# USB.net
KiCad netlist of a schematic drawn in Altium Designer
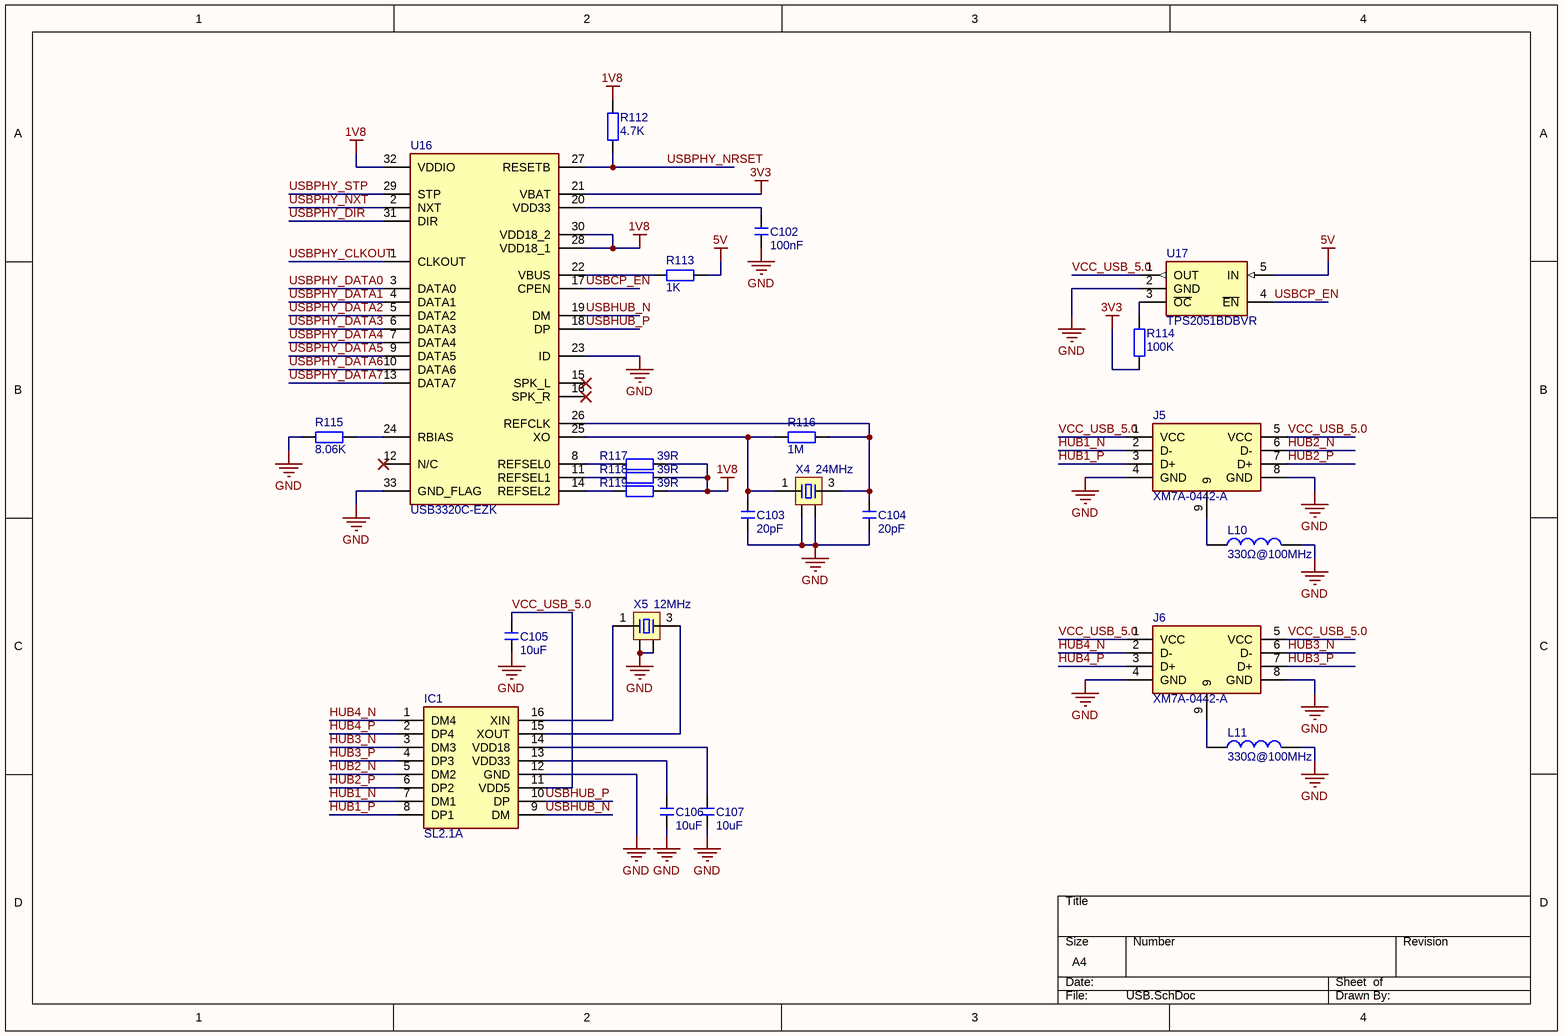
[diagram p0: USB.SchDoc]

(export (version "E")
  (design (tool "Eeschema 10.0.6"))
  (components
    (comp (ref "C102")
      (value "100nF")
      (footprint "C 0402_L")
      (description "无极性贴片电容")
      (fields (field (name "版权归属") "源创客"))
      (libsource (lib "3.1   - 电阻-电容-电感") (part "C"))
    )
    (comp (ref "C103")
      (value "20pF")
      (footprint "C 0805_L")
      (description "无极性贴片电容")
      (fields (field (name "版权归属") "源创客"))
      (libsource (lib "3.1   - 电阻-电容-电感") (part "C"))
    )
    (comp (ref "C104")
      (value "20pF")
      (footprint "C 0805_L")
      (description "无极性贴片电容")
      (fields (field (name "版权归属") "源创客"))
      (libsource (lib "3.1   - 电阻-电容-电感") (part "C"))
    )
    (comp (ref "C105")
      (value "10uF")
      (footprint "C 0603_L")
      (description "无极性贴片电容")
      (fields (field (name "版权归属") "源创客"))
      (libsource (lib "3.1   - 电阻-电容-电感") (part "C"))
    )
    (comp (ref "C106")
      (value "10uF")
      (footprint "C 0603_L")
      (description "无极性贴片电容")
      (fields (field (name "版权归属") "源创客"))
      (libsource (lib "3.1   - 电阻-电容-电感") (part "C"))
    )
    (comp (ref "C107")
      (value "10uF")
      (footprint "C 0603_L")
      (description "无极性贴片电容")
      (fields (field (name "版权归属") "源创客"))
      (libsource (lib "3.1   - 电阻-电容-电感") (part "C"))
    )
    (comp (ref "IC1")
      (value "SL2.1A")
      (footprint "SOP16N_L")
      (description "Integrated Circuit")
      (libsource (lib "1.1   - IC芯片") (part "SL2.1A"))
    )
    (comp (ref "J5")
      (value "XM7A-0442-A")
      (footprint "XM7A0442A")
      (description "USB2.0-A双层")
      (fields (field (name "MOUSER PART NUMBER") "653-XM7A-0442A"))
      (libsource (lib "4.1   - 接口类") (part "XM7A-0442-A"))
    )
    (comp (ref "J6")
      (value "XM7A-0442-A")
      (footprint "XM7A0442A")
      (description "USB2.0-A双层")
      (fields (field (name "MOUSER PART NUMBER") "653-XM7A-0442A"))
      (libsource (lib "4.1   - 接口类") (part "XM7A-0442-A"))
    )
    (comp (ref "L10")
      (value "330Ω@100MHz")
      (footprint "L 0805")
      (description "小功率贴片电感")
      (fields (field (name "版权归属") "源创客"))
      (libsource (lib "3.1   - 电阻-电容-电感") (part "L"))
    )
    (comp (ref "L11")
      (value "330Ω@100MHz")
      (footprint "L 0805")
      (description "小功率贴片电感")
      (fields (field (name "版权归属") "源创客"))
      (libsource (lib "3.1   - 电阻-电容-电感") (part "L"))
    )
    (comp (ref "R112")
      (value "4.7K")
      (footprint "R 0402_L")
      (description "贴片电阻")
      (fields (field (name "版权归属") "源创客"))
      (libsource (lib "3.1   - 电阻-电容-电感") (part "R"))
    )
    (comp (ref "R113")
      (value "1K")
      (footprint "R 0402_L")
      (description "贴片电阻")
      (fields (field (name "版权归属") "源创客"))
      (libsource (lib "3.1   - 电阻-电容-电感") (part "R"))
    )
    (comp (ref "R114")
      (value "100K")
      (footprint "R 0805_L")
      (description "贴片电阻")
      (fields (field (name "版权归属") "源创客"))
      (libsource (lib "3.1   - 电阻-电容-电感") (part "R"))
    )
    (comp (ref "R115")
      (value "8.06K")
      (footprint "R 0402_L")
      (description "贴片电阻")
      (fields (field (name "版权归属") "源创客"))
      (libsource (lib "3.1   - 电阻-电容-电感") (part "R"))
    )
    (comp (ref "R116")
      (value "1M")
      (footprint "R 0402_L")
      (description "贴片电阻")
      (fields (field (name "版权归属") "源创客"))
      (libsource (lib "3.1   - 电阻-电容-电感") (part "R"))
    )
    (comp (ref "R117")
      (value "39R")
      (footprint "R 0805_L")
      (description "贴片电阻")
      (fields (field (name "版权归属") "源创客"))
      (libsource (lib "3.1   - 电阻-电容-电感") (part "R"))
    )
    (comp (ref "R118")
      (value "39R")
      (footprint "R 0805_L")
      (description "贴片电阻")
      (fields (field (name "版权归属") "源创客"))
      (libsource (lib "3.1   - 电阻-电容-电感") (part "R"))
    )
    (comp (ref "R119")
      (value "39R")
      (footprint "R 0805_L")
      (description "贴片电阻")
      (fields (field (name "版权归属") "源创客"))
      (libsource (lib "3.1   - 电阻-电容-电感") (part "R"))
    )
    (comp (ref "U16")
      (value "USB3320C-EZK")
      (footprint "QFN32 5x5_M")
      (description "USB集线芯片")
      (fields (field (name "MOUSER PART NUMBER") "886-USB3320C-EZK"))
      (libsource (lib "1.1   - IC芯片") (part "USB3320C-EZK"))
    )
    (comp (ref "U17")
      (value "TPS2051BDBVR")
      (footprint "SOT23-5N")
      (description "模拟开关芯片")
      (fields (field (name "MOUSER PART NUMBER") "595-TPS2051BDBVR"))
      (libsource (lib "1.1   - IC芯片") (part "TPS2051BDBVR"))
    )
    (comp (ref "X4")
      (value "24MHz")
      (footprint "OSC 1612-4P")
      (description "4脚无源晶振")
      (fields (field (name "版权归属") "源创客"))
      (libsource (lib "10.1 - 保险丝-晶振") (part "XTAL-4P"))
    )
    (comp (ref "X5")
      (value "12MHz")
      (footprint "OSC 1612-4P")
      (description "4脚无源晶振")
      (fields (field (name "版权归属") "源创客"))
      (libsource (lib "10.1 - 保险丝-晶振") (part "XTAL-4P"))
    )
  )
  (nets
    (net (code "1") (name "/HUB1_N") (class "Default")
      (node (ref "IC1") (pin "7") (pinfunction "DM1_7") (pintype "passive"))
      (node (ref "J5") (pin "2") (pinfunction "D-_2") (pintype "passive"))
    )
    (net (code "2") (name "/HUB1_P") (class "Default")
      (node (ref "IC1") (pin "8") (pinfunction "DP1_8") (pintype "passive"))
      (node (ref "J5") (pin "3") (pinfunction "D+_3") (pintype "passive"))
    )
    (net (code "3") (name "/HUB2_N") (class "Default")
      (node (ref "IC1") (pin "5") (pinfunction "DM2_5") (pintype "passive"))
      (node (ref "J5") (pin "6") (pinfunction "D-_6") (pintype "passive"))
    )
    (net (code "4") (name "/HUB2_P") (class "Default")
      (node (ref "IC1") (pin "6") (pinfunction "DP2_6") (pintype "passive"))
      (node (ref "J5") (pin "7") (pinfunction "D+_7") (pintype "passive"))
    )
    (net (code "5") (name "/HUB3_N") (class "Default")
      (node (ref "IC1") (pin "3") (pinfunction "DM3_3") (pintype "passive"))
      (node (ref "J6") (pin "6") (pinfunction "D-_6") (pintype "passive"))
    )
    (net (code "6") (name "/HUB3_P") (class "Default")
      (node (ref "IC1") (pin "4") (pinfunction "DP3_4") (pintype "passive"))
      (node (ref "J6") (pin "7") (pinfunction "D+_7") (pintype "passive"))
    )
    (net (code "7") (name "/HUB4_N") (class "Default")
      (node (ref "IC1") (pin "1") (pinfunction "DM4_1") (pintype "passive"))
      (node (ref "J6") (pin "2") (pinfunction "D-_2") (pintype "passive"))
    )
    (net (code "8") (name "/HUB4_P") (class "Default")
      (node (ref "IC1") (pin "2") (pinfunction "DP4_2") (pintype "passive"))
      (node (ref "J6") (pin "3") (pinfunction "D+_3") (pintype "passive"))
    )
    (net (code "9") (name "/USBCP_EN") (class "Default")
      (node (ref "U16") (pin "17") (pinfunction "CPEN_17") (pintype "passive"))
      (node (ref "U17") (pin "4") (pinfunction "~{EN}_4") (pintype "passive"))
    )
    (net (code "10") (name "/USBHUB_N") (class "Default")
      (node (ref "IC1") (pin "9") (pinfunction "DM_9") (pintype "passive"))
      (node (ref "U16") (pin "19") (pinfunction "DM_19") (pintype "passive"))
    )
    (net (code "11") (name "/USBHUB_P") (class "Default")
      (node (ref "IC1") (pin "10") (pinfunction "DP_10") (pintype "passive"))
      (node (ref "U16") (pin "18") (pinfunction "DP_18") (pintype "passive"))
    )
    (net (code "12") (name "/USBPHY_CLKOUT") (class "Default")
      (node (ref "U16") (pin "1") (pinfunction "CLKOUT_1") (pintype "passive"))
    )
    (net (code "13") (name "/USBPHY_DATA0") (class "Default")
      (node (ref "U16") (pin "3") (pinfunction "DATA0_3") (pintype "passive"))
    )
    (net (code "14") (name "/USBPHY_DATA1") (class "Default")
      (node (ref "U16") (pin "4") (pinfunction "DATA1_4") (pintype "passive"))
    )
    (net (code "15") (name "/USBPHY_DATA2") (class "Default")
      (node (ref "U16") (pin "5") (pinfunction "DATA2_5") (pintype "passive"))
    )
    (net (code "16") (name "/USBPHY_DATA3") (class "Default")
      (node (ref "U16") (pin "6") (pinfunction "DATA3_6") (pintype "passive"))
    )
    (net (code "17") (name "/USBPHY_DATA4") (class "Default")
      (node (ref "U16") (pin "7") (pinfunction "DATA4_7") (pintype "passive"))
    )
    (net (code "18") (name "/USBPHY_DATA5") (class "Default")
      (node (ref "U16") (pin "9") (pinfunction "DATA5_9") (pintype "passive"))
    )
    (net (code "19") (name "/USBPHY_DATA6") (class "Default")
      (node (ref "U16") (pin "10") (pinfunction "DATA6_10") (pintype "passive"))
    )
    (net (code "20") (name "/USBPHY_DATA7") (class "Default")
      (node (ref "U16") (pin "13") (pinfunction "DATA7_13") (pintype "passive"))
    )
    (net (code "21") (name "/USBPHY_DIR") (class "Default")
      (node (ref "U16") (pin "31") (pinfunction "DIR_31") (pintype "passive"))
    )
    (net (code "22") (name "/USBPHY_NRSET") (class "Default")
      (node (ref "R112") (pin "1") (pinfunction "1_1") (pintype "passive"))
      (node (ref "U16") (pin "27") (pinfunction "RESETB_27") (pintype "passive"))
    )
    (net (code "23") (name "/USBPHY_NXT") (class "Default")
      (node (ref "U16") (pin "2") (pinfunction "NXT_2") (pintype "passive"))
    )
    (net (code "24") (name "/USBPHY_STP") (class "Default")
      (node (ref "U16") (pin "29") (pinfunction "STP_29") (pintype "passive"))
    )
    (net (code "25") (name "/VCC_USB_5.0") (class "Default")
      (node (ref "C105") (pin "2") (pinfunction "2_2") (pintype "passive"))
      (node (ref "IC1") (pin "11") (pinfunction "VDD5_11") (pintype "passive"))
      (node (ref "J5") (pin "1") (pinfunction "VCC_1") (pintype "passive"))
      (node (ref "J5") (pin "5") (pinfunction "VCC_5") (pintype "passive"))
      (node (ref "J6") (pin "1") (pinfunction "VCC_1") (pintype "passive"))
      (node (ref "J6") (pin "5") (pinfunction "VCC_5") (pintype "passive"))
      (node (ref "U17") (pin "1") (pinfunction "OUT_1") (pintype "output"))
    )
    (net (code "26") (name "1V8") (class "Default")
      (node (ref "R112") (pin "2") (pinfunction "2_2") (pintype "passive"))
      (node (ref "R117") (pin "1") (pinfunction "1_1") (pintype "passive"))
      (node (ref "R118") (pin "1") (pinfunction "1_1") (pintype "passive"))
      (node (ref "R119") (pin "1") (pinfunction "1_1") (pintype "passive"))
      (node (ref "U16") (pin "28") (pinfunction "VDD18_1_28") (pintype "passive"))
      (node (ref "U16") (pin "30") (pinfunction "VDD18_2_30") (pintype "passive"))
      (node (ref "U16") (pin "32") (pinfunction "VDDIO_32") (pintype "passive"))
    )
    (net (code "27") (name "3V3") (class "Default")
      (node (ref "R114") (pin "1") (pinfunction "1_1") (pintype "passive"))
      (node (ref "U16") (pin "21") (pinfunction "VBAT_21") (pintype "passive"))
    )
    (net (code "28") (name "5V") (class "Default")
      (node (ref "R113") (pin "1") (pinfunction "1_1") (pintype "passive"))
      (node (ref "U17") (pin "5") (pinfunction "IN_5") (pintype "input"))
    )
    (net (code "29") (name "GND") (class "Default")
      (node (ref "C102") (pin "1") (pinfunction "1_1") (pintype "passive"))
      (node (ref "C103") (pin "1") (pinfunction "1_1") (pintype "passive"))
      (node (ref "C104") (pin "1") (pinfunction "1_1") (pintype "passive"))
      (node (ref "C105") (pin "1") (pinfunction "1_1") (pintype "passive"))
      (node (ref "C106") (pin "1") (pinfunction "1_1") (pintype "passive"))
      (node (ref "C107") (pin "1") (pinfunction "1_1") (pintype "passive"))
      (node (ref "IC1") (pin "12") (pinfunction "GND_12") (pintype "passive"))
      (node (ref "J5") (pin "4") (pinfunction "GND_4") (pintype "passive"))
      (node (ref "J5") (pin "8") (pinfunction "GND_8") (pintype "passive"))
      (node (ref "J6") (pin "4") (pinfunction "GND_4") (pintype "passive"))
      (node (ref "J6") (pin "8") (pinfunction "GND_8") (pintype "passive"))
      (node (ref "L10") (pin "2") (pinfunction "2_2") (pintype "passive"))
      (node (ref "L11") (pin "2") (pinfunction "2_2") (pintype "passive"))
      (node (ref "R115") (pin "1") (pinfunction "1_1") (pintype "passive"))
      (node (ref "U16") (pin "23") (pinfunction "ID_23") (pintype "passive"))
      (node (ref "U16") (pin "33") (pinfunction "GND_FLAG_33") (pintype "passive"))
      (node (ref "U17") (pin "2") (pinfunction "GND_2") (pintype "power_in"))
      (node (ref "X4") (pin "2") (pinfunction "2_2") (pintype "passive"))
      (node (ref "X4") (pin "4") (pinfunction "4_4") (pintype "passive"))
      (node (ref "X5") (pin "2") (pinfunction "2_2") (pintype "passive"))
      (node (ref "X5") (pin "4") (pinfunction "4_4") (pintype "passive"))
    )
    (net (code "30") (name "Net-(IC1-VDD18)") (class "Default")
      (node (ref "C107") (pin "2") (pinfunction "2_2") (pintype "passive"))
      (node (ref "IC1") (pin "14") (pinfunction "VDD18_14") (pintype "passive"))
    )
    (net (code "31") (name "Net-(IC1-VDD33)") (class "Default")
      (node (ref "C106") (pin "2") (pinfunction "2_2") (pintype "passive"))
      (node (ref "IC1") (pin "13") (pinfunction "VDD33_13") (pintype "passive"))
    )
    (net (code "32") (name "Net-(IC1-XIN)") (class "Default")
      (node (ref "IC1") (pin "16") (pinfunction "XIN_16") (pintype "passive"))
      (node (ref "X5") (pin "1") (pinfunction "1_1") (pintype "passive"))
    )
    (net (code "33") (name "Net-(IC1-XOUT)") (class "Default")
      (node (ref "IC1") (pin "15") (pinfunction "XOUT_15") (pintype "passive"))
      (node (ref "X5") (pin "3") (pinfunction "3_3") (pintype "passive"))
    )
    (net (code "34") (name "Net-(J5-Pad9)") (class "Default")
      (node (ref "J5") (pin "9") (pinfunction "9_9") (pintype "passive"))
      (node (ref "L10") (pin "1") (pinfunction "1_1") (pintype "passive"))
    )
    (net (code "35") (name "Net-(J6-Pad9)") (class "Default")
      (node (ref "J6") (pin "9") (pinfunction "9_9") (pintype "passive"))
      (node (ref "L11") (pin "1") (pinfunction "1_1") (pintype "passive"))
    )
    (net (code "36") (name "Net-(U16-RBIAS)") (class "Default")
      (node (ref "R115") (pin "2") (pinfunction "2_2") (pintype "passive"))
      (node (ref "U16") (pin "24") (pinfunction "RBIAS_24") (pintype "passive"))
    )
    (net (code "37") (name "Net-(U16-REFCLK)") (class "Default")
      (node (ref "C104") (pin "2") (pinfunction "2_2") (pintype "passive"))
      (node (ref "R116") (pin "2") (pinfunction "2_2") (pintype "passive"))
      (node (ref "U16") (pin "26") (pinfunction "REFCLK_26") (pintype "passive"))
      (node (ref "X4") (pin "3") (pinfunction "3_3") (pintype "passive"))
    )
    (net (code "38") (name "Net-(U16-REFSEL0)") (class "Default")
      (node (ref "R117") (pin "2") (pinfunction "2_2") (pintype "passive"))
      (node (ref "U16") (pin "8") (pinfunction "REFSEL0_8") (pintype "passive"))
    )
    (net (code "39") (name "Net-(U16-REFSEL1)") (class "Default")
      (node (ref "R118") (pin "2") (pinfunction "2_2") (pintype "passive"))
      (node (ref "U16") (pin "11") (pinfunction "REFSEL1_11") (pintype "passive"))
    )
    (net (code "40") (name "Net-(U16-REFSEL2)") (class "Default")
      (node (ref "R119") (pin "2") (pinfunction "2_2") (pintype "passive"))
      (node (ref "U16") (pin "14") (pinfunction "REFSEL2_14") (pintype "passive"))
    )
    (net (code "41") (name "Net-(U16-VBUS)") (class "Default")
      (node (ref "R113") (pin "2") (pinfunction "2_2") (pintype "passive"))
      (node (ref "U16") (pin "22") (pinfunction "VBUS_22") (pintype "passive"))
    )
    (net (code "42") (name "Net-(U16-VDD33)") (class "Default")
      (node (ref "C102") (pin "2") (pinfunction "2_2") (pintype "passive"))
      (node (ref "U16") (pin "20") (pinfunction "VDD33_20") (pintype "passive"))
    )
    (net (code "43") (name "Net-(U16-XO)") (class "Default")
      (node (ref "C103") (pin "2") (pinfunction "2_2") (pintype "passive"))
      (node (ref "R116") (pin "1") (pinfunction "1_1") (pintype "passive"))
      (node (ref "U16") (pin "25") (pinfunction "XO_25") (pintype "passive"))
      (node (ref "X4") (pin "1") (pinfunction "1_1") (pintype "passive"))
    )
    (net (code "44") (name "Net-(U17-~{OC})") (class "Default")
      (node (ref "R114") (pin "2") (pinfunction "2_2") (pintype "passive"))
      (node (ref "U17") (pin "3") (pinfunction "~{OC}_3") (pintype "passive"))
    )
    (net (code "45") (name "unconnected-(U16-N{slash}C-Pad12)") (class "Default")
      (node (ref "U16") (pin "12") (pinfunction "N/C_12") (pintype "passive+no_connect"))
    )
    (net (code "46") (name "unconnected-(U16-SPK_L-Pad15)") (class "Default")
      (node (ref "U16") (pin "15") (pinfunction "SPK_L_15") (pintype "passive+no_connect"))
    )
    (net (code "47") (name "unconnected-(U16-SPK_R-Pad16)") (class "Default")
      (node (ref "U16") (pin "16") (pinfunction "SPK_R_16") (pintype "passive+no_connect"))
    )
  )
)
